# LVHV8ChanTranslation.net
KiCad netlist of a schematic drawn in Altium Designer
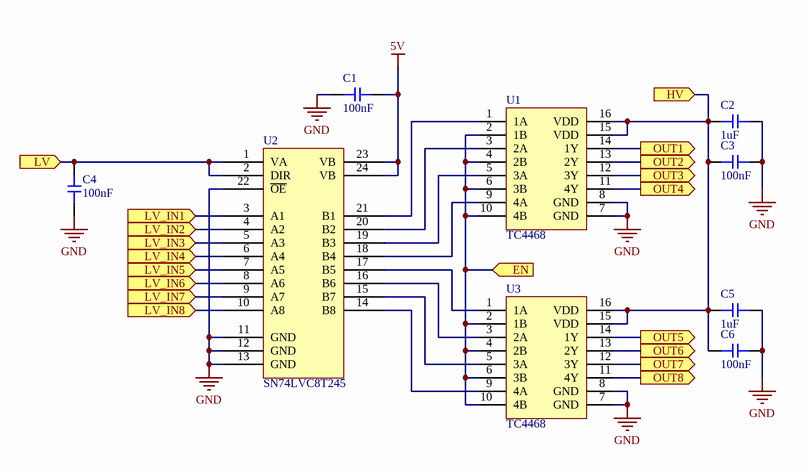
[diagram p0: LVHV8ChanTranslation.SchDoc]

(export (version "E")
  (design (tool "Eeschema 10.0.6"))
  (components
    (comp (ref "C1")
      (value "100nF")
      (footprint "AMDC:0603-CAP")
      (description "Capacitor")
      (libsource (lib "AMDC") (part "Capacitor"))
    )
    (comp (ref "C2")
      (value "1uF")
      (footprint "AMDC:0603-CAP")
      (description "Capacitor")
      (libsource (lib "AMDC") (part "Capacitor"))
    )
    (comp (ref "C3")
      (value "100nF")
      (footprint "AMDC:0603-CAP")
      (description "Capacitor")
      (libsource (lib "AMDC") (part "Capacitor"))
    )
    (comp (ref "C4")
      (value "100nF")
      (footprint "AMDC:0603-CAP")
      (description "Capacitor")
      (libsource (lib "AMDC") (part "Capacitor"))
    )
    (comp (ref "C5")
      (value "1uF")
      (footprint "AMDC:0603-CAP")
      (description "Capacitor")
      (libsource (lib "AMDC") (part "Capacitor"))
    )
    (comp (ref "C6")
      (value "100nF")
      (footprint "AMDC:0603-CAP")
      (description "Capacitor")
      (libsource (lib "AMDC") (part "Capacitor"))
    )
    (comp (ref "U1")
      (value "TC4468")
      (footprint "AMDC:SOIC16_N - wide")
      (description "IC MOSFET DVR QUAD AND 16SOIC")
      (libsource (lib "AMDC") (part "TC4468"))
    )
    (comp (ref "U2")
      (value "SN74LVC8T245")
      (footprint "AMDC:TSOP65P640X120-24N")
      (description "IC BUS TRANSCVR 8BIT 24TSSOP")
      (libsource (lib "AMDC") (part "SN74LVC8T245PWR"))
    )
    (comp (ref "U3")
      (value "TC4468")
      (footprint "AMDC:SOIC16_N - wide")
      (description "IC MOSFET DVR QUAD AND 16SOIC")
      (libsource (lib "AMDC") (part "TC4468"))
    )
  )
  (nets
    (net (code "1") (name "/EN") (class "Default")
      (node (ref "U1") (pin "10") (pinfunction "4B_10") (pintype "passive"))
      (node (ref "U1") (pin "2") (pinfunction "1B_2") (pintype "passive"))
      (node (ref "U1") (pin "4") (pinfunction "2B_4") (pintype "passive"))
      (node (ref "U1") (pin "6") (pinfunction "3B_6") (pintype "passive"))
      (node (ref "U3") (pin "10") (pinfunction "4B_10") (pintype "passive"))
      (node (ref "U3") (pin "2") (pinfunction "1B_2") (pintype "passive"))
      (node (ref "U3") (pin "4") (pinfunction "2B_4") (pintype "passive"))
      (node (ref "U3") (pin "6") (pinfunction "3B_6") (pintype "passive"))
    )
    (net (code "2") (name "/HV") (class "Default")
      (node (ref "C2") (pin "1") (pinfunction "1_1") (pintype "passive"))
      (node (ref "C3") (pin "1") (pinfunction "1_1") (pintype "passive"))
      (node (ref "C5") (pin "1") (pinfunction "1_1") (pintype "passive"))
      (node (ref "C6") (pin "1") (pinfunction "1_1") (pintype "passive"))
      (node (ref "U1") (pin "15") (pinfunction "VDD_15") (pintype "passive"))
      (node (ref "U1") (pin "16") (pinfunction "VDD_16") (pintype "passive"))
      (node (ref "U3") (pin "15") (pinfunction "VDD_15") (pintype "passive"))
      (node (ref "U3") (pin "16") (pinfunction "VDD_16") (pintype "passive"))
    )
    (net (code "3") (name "/LV") (class "Default")
      (node (ref "C4") (pin "2") (pinfunction "2_2") (pintype "passive"))
      (node (ref "U2") (pin "1") (pinfunction "VA_1") (pintype "passive"))
      (node (ref "U2") (pin "2") (pinfunction "DIR_2") (pintype "passive"))
    )
    (net (code "4") (name "/LV_IN1") (class "Default")
      (node (ref "U2") (pin "3") (pinfunction "A1_3") (pintype "passive"))
    )
    (net (code "5") (name "/LV_IN2") (class "Default")
      (node (ref "U2") (pin "4") (pinfunction "A2_4") (pintype "passive"))
    )
    (net (code "6") (name "/LV_IN3") (class "Default")
      (node (ref "U2") (pin "5") (pinfunction "A3_5") (pintype "passive"))
    )
    (net (code "7") (name "/LV_IN4") (class "Default")
      (node (ref "U2") (pin "6") (pinfunction "A4_6") (pintype "passive"))
    )
    (net (code "8") (name "/LV_IN5") (class "Default")
      (node (ref "U2") (pin "7") (pinfunction "A5_7") (pintype "passive"))
    )
    (net (code "9") (name "/LV_IN6") (class "Default")
      (node (ref "U2") (pin "8") (pinfunction "A6_8") (pintype "passive"))
    )
    (net (code "10") (name "/LV_IN7") (class "Default")
      (node (ref "U2") (pin "9") (pinfunction "A7_9") (pintype "passive"))
    )
    (net (code "11") (name "/LV_IN8") (class "Default")
      (node (ref "U2") (pin "10") (pinfunction "A8_10") (pintype "passive"))
    )
    (net (code "12") (name "/OUT1") (class "Default")
      (node (ref "U1") (pin "14") (pinfunction "1Y_14") (pintype "passive"))
    )
    (net (code "13") (name "/OUT2") (class "Default")
      (node (ref "U1") (pin "13") (pinfunction "2Y_13") (pintype "passive"))
    )
    (net (code "14") (name "/OUT3") (class "Default")
      (node (ref "U1") (pin "12") (pinfunction "3Y_12") (pintype "passive"))
    )
    (net (code "15") (name "/OUT4") (class "Default")
      (node (ref "U1") (pin "11") (pinfunction "4Y_11") (pintype "passive"))
    )
    (net (code "16") (name "/OUT5") (class "Default")
      (node (ref "U3") (pin "14") (pinfunction "1Y_14") (pintype "passive"))
    )
    (net (code "17") (name "/OUT6") (class "Default")
      (node (ref "U3") (pin "13") (pinfunction "2Y_13") (pintype "passive"))
    )
    (net (code "18") (name "/OUT7") (class "Default")
      (node (ref "U3") (pin "12") (pinfunction "3Y_12") (pintype "passive"))
    )
    (net (code "19") (name "/OUT8") (class "Default")
      (node (ref "U3") (pin "11") (pinfunction "4Y_11") (pintype "passive"))
    )
    (net (code "20") (name "5V") (class "Default")
      (node (ref "C1") (pin "1") (pinfunction "1_1") (pintype "passive"))
      (node (ref "U2") (pin "23") (pinfunction "VB_23") (pintype "passive"))
      (node (ref "U2") (pin "24") (pinfunction "VB_24") (pintype "passive"))
    )
    (net (code "21") (name "GND") (class "Default")
      (node (ref "C1") (pin "2") (pinfunction "2_2") (pintype "passive"))
      (node (ref "C2") (pin "2") (pinfunction "2_2") (pintype "passive"))
      (node (ref "C3") (pin "2") (pinfunction "2_2") (pintype "passive"))
      (node (ref "C4") (pin "1") (pinfunction "1_1") (pintype "passive"))
      (node (ref "C5") (pin "2") (pinfunction "2_2") (pintype "passive"))
      (node (ref "C6") (pin "2") (pinfunction "2_2") (pintype "passive"))
      (node (ref "U1") (pin "7") (pinfunction "GND_7") (pintype "passive"))
      (node (ref "U1") (pin "8") (pinfunction "GND_8") (pintype "passive"))
      (node (ref "U2") (pin "11") (pinfunction "GND_11") (pintype "passive"))
      (node (ref "U2") (pin "12") (pinfunction "GND_12") (pintype "passive"))
      (node (ref "U2") (pin "13") (pinfunction "GND_13") (pintype "passive"))
      (node (ref "U2") (pin "22") (pinfunction "~{OE}_22") (pintype "passive"))
      (node (ref "U3") (pin "7") (pinfunction "GND_7") (pintype "passive"))
      (node (ref "U3") (pin "8") (pinfunction "GND_8") (pintype "passive"))
    )
    (net (code "22") (name "Net-(U1-1A)") (class "Default")
      (node (ref "U1") (pin "1") (pinfunction "1A_1") (pintype "passive"))
      (node (ref "U2") (pin "21") (pinfunction "B1_21") (pintype "passive"))
    )
    (net (code "23") (name "Net-(U1-2A)") (class "Default")
      (node (ref "U1") (pin "3") (pinfunction "2A_3") (pintype "passive"))
      (node (ref "U2") (pin "20") (pinfunction "B2_20") (pintype "passive"))
    )
    (net (code "24") (name "Net-(U1-3A)") (class "Default")
      (node (ref "U1") (pin "5") (pinfunction "3A_5") (pintype "passive"))
      (node (ref "U2") (pin "19") (pinfunction "B3_19") (pintype "passive"))
    )
    (net (code "25") (name "Net-(U1-4A)") (class "Default")
      (node (ref "U1") (pin "9") (pinfunction "4A_9") (pintype "passive"))
      (node (ref "U2") (pin "18") (pinfunction "B4_18") (pintype "passive"))
    )
    (net (code "26") (name "Net-(U2-B5)") (class "Default")
      (node (ref "U2") (pin "17") (pinfunction "B5_17") (pintype "passive"))
      (node (ref "U3") (pin "1") (pinfunction "1A_1") (pintype "passive"))
    )
    (net (code "27") (name "Net-(U2-B6)") (class "Default")
      (node (ref "U2") (pin "16") (pinfunction "B6_16") (pintype "passive"))
      (node (ref "U3") (pin "3") (pinfunction "2A_3") (pintype "passive"))
    )
    (net (code "28") (name "Net-(U2-B7)") (class "Default")
      (node (ref "U2") (pin "15") (pinfunction "B7_15") (pintype "passive"))
      (node (ref "U3") (pin "5") (pinfunction "3A_5") (pintype "passive"))
    )
    (net (code "29") (name "Net-(U2-B8)") (class "Default")
      (node (ref "U2") (pin "14") (pinfunction "B8_14") (pintype "passive"))
      (node (ref "U3") (pin "9") (pinfunction "4A_9") (pintype "passive"))
    )
  )
)
